# Placa_sensores.net
KiCad netlist of a schematic drawn in EAGLE
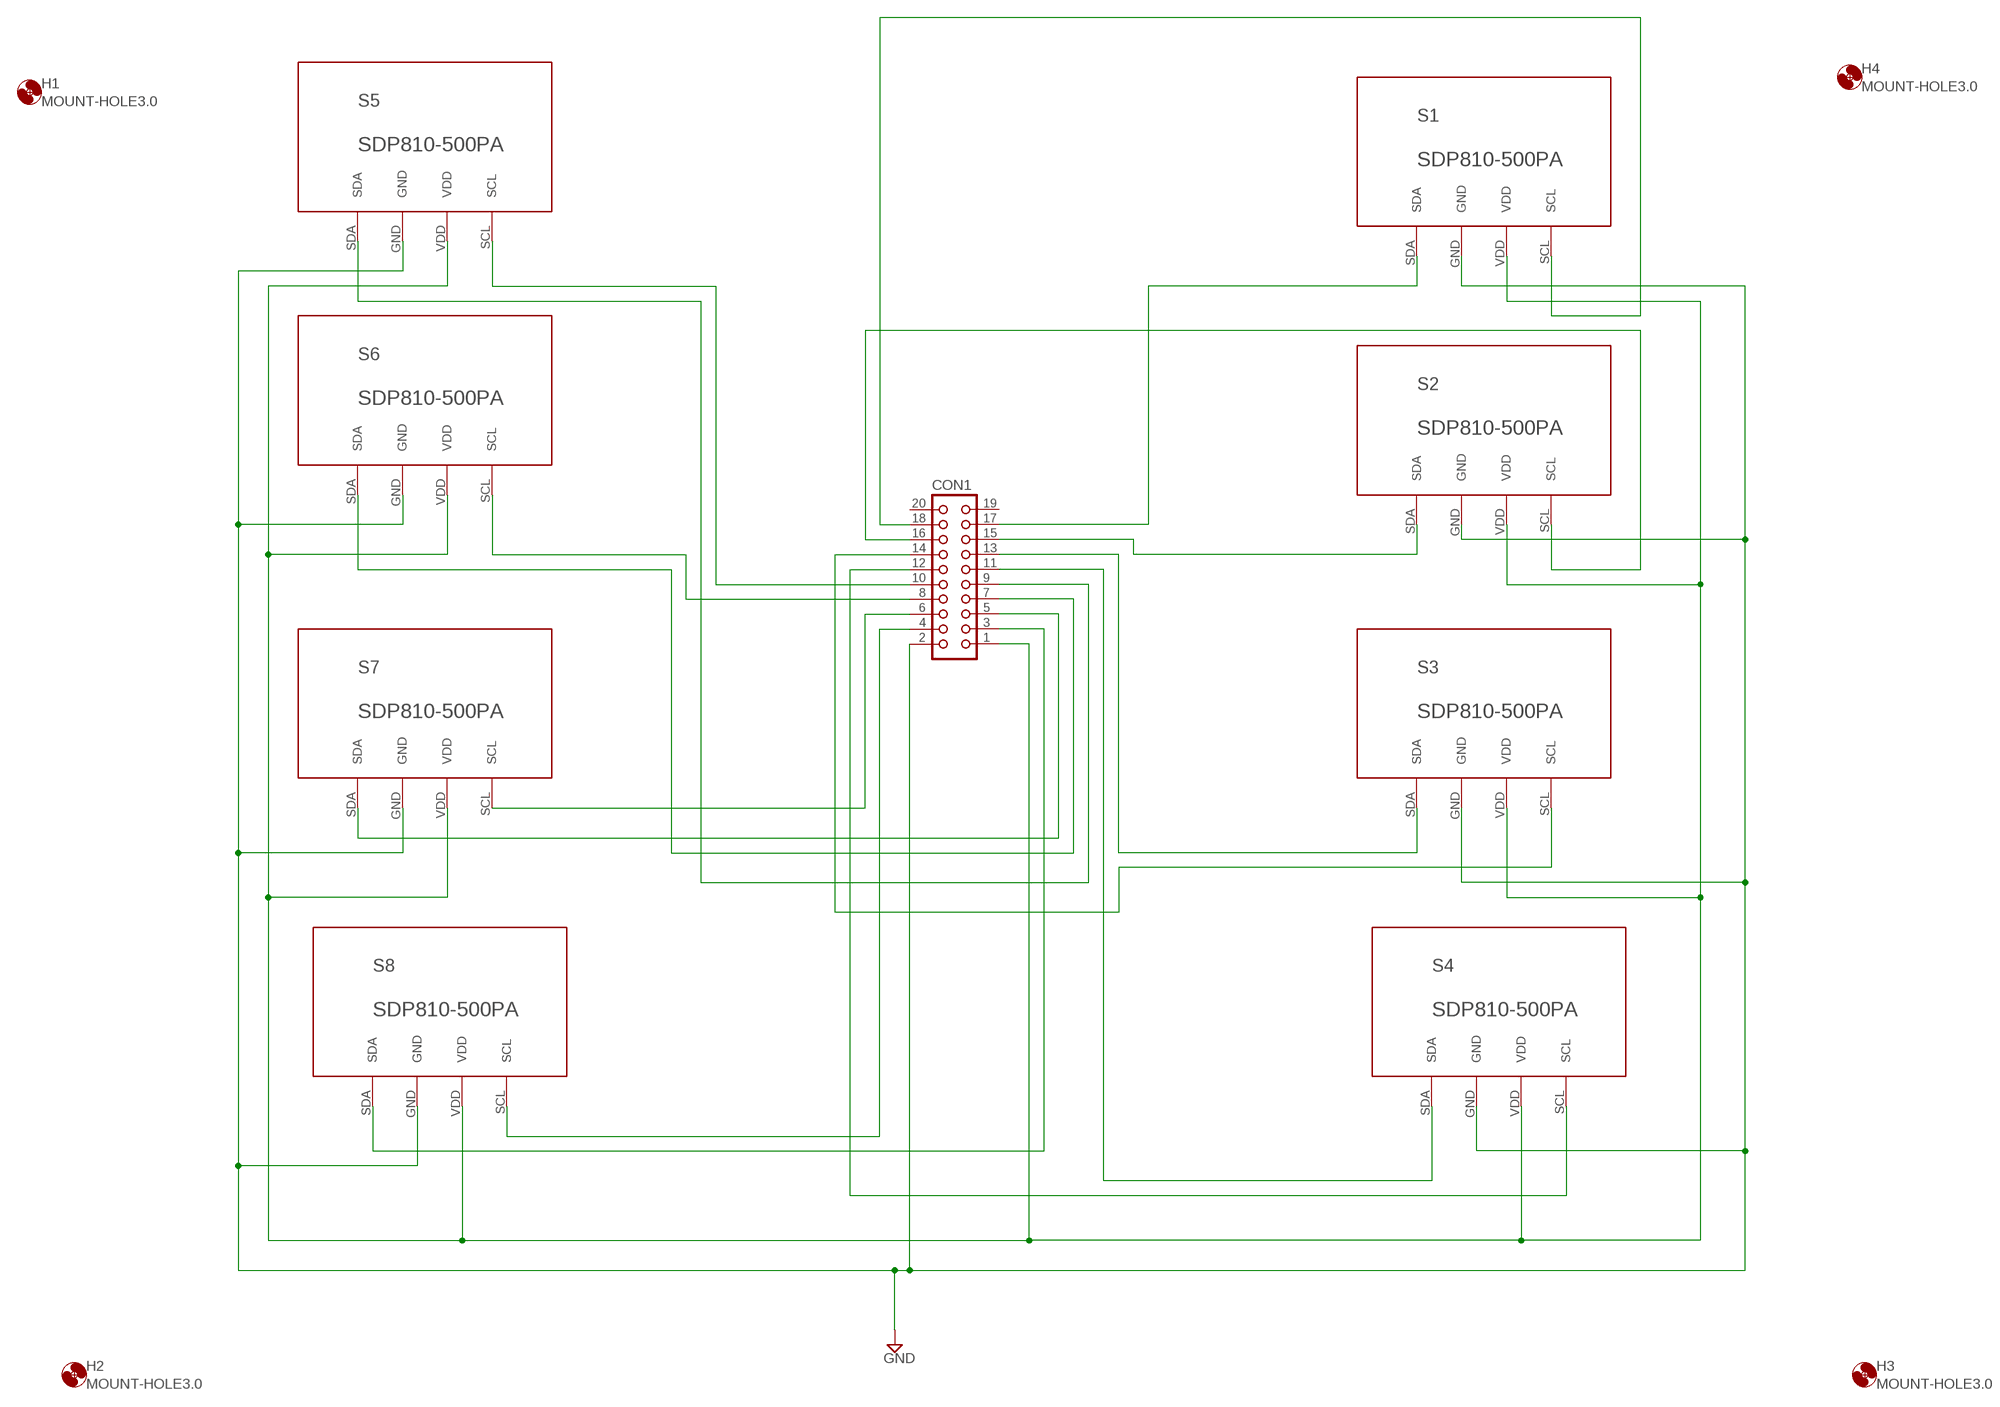
[diagram p0: schematic, sheet 1]

(export (version "E")
  (design (tool "Eeschema 10.0.6"))
  (components
    (comp (ref "CON1")
      (value "CON20")
      (footprint "eagle-import:CON20")
      (libsource (lib "eagle-import") (part "CON20"))
    )
    (comp (ref "H1")
      (value "MOUNT-HOLE3.0")
      (footprint "eagle-import:3,0")
      (libsource (lib "eagle-import") (part "MOUNT-HOLE3.0"))
    )
    (comp (ref "H2")
      (value "MOUNT-HOLE3.0")
      (footprint "eagle-import:3,0")
      (libsource (lib "eagle-import") (part "MOUNT-HOLE3.0"))
    )
    (comp (ref "H3")
      (value "MOUNT-HOLE3.0")
      (footprint "eagle-import:3,0")
      (libsource (lib "eagle-import") (part "MOUNT-HOLE3.0"))
    )
    (comp (ref "H4")
      (value "MOUNT-HOLE3.0")
      (footprint "eagle-import:3,0")
      (libsource (lib "eagle-import") (part "MOUNT-HOLE3.0"))
    )
    (comp (ref "S1")
      (value "SDP810-500PA")
      (footprint "eagle-import:SDP810-500PA")
      (libsource (lib "eagle-import") (part "SDP810-500PA"))
    )
    (comp (ref "S2")
      (value "SDP810-500PA")
      (footprint "eagle-import:SDP810-500PA")
      (libsource (lib "eagle-import") (part "SDP810-500PA"))
    )
    (comp (ref "S3")
      (value "SDP810-500PA")
      (footprint "eagle-import:SDP810-500PA")
      (libsource (lib "eagle-import") (part "SDP810-500PA"))
    )
    (comp (ref "S4")
      (value "SDP810-500PA")
      (footprint "eagle-import:SDP810-500PA")
      (libsource (lib "eagle-import") (part "SDP810-500PA"))
    )
    (comp (ref "S5")
      (value "SDP810-500PA")
      (footprint "eagle-import:SDP810-500PA")
      (libsource (lib "eagle-import") (part "SDP810-500PA"))
    )
    (comp (ref "S6")
      (value "SDP810-500PA")
      (footprint "eagle-import:SDP810-500PA")
      (libsource (lib "eagle-import") (part "SDP810-500PA"))
    )
    (comp (ref "S7")
      (value "SDP810-500PA")
      (footprint "eagle-import:SDP810-500PA")
      (libsource (lib "eagle-import") (part "SDP810-500PA"))
    )
    (comp (ref "S8")
      (value "SDP810-500PA")
      (footprint "eagle-import:SDP810-500PA")
      (libsource (lib "eagle-import") (part "SDP810-500PA"))
    )
  )
  (nets
    (net (code "1") (name "GND") (class "Default")
      (node (ref "CON1") (pin "2") (pinfunction "2_2") (pintype "passive"))
      (node (ref "S1") (pin "GND") (pinfunction "GND_GND") (pintype "bidirectional"))
      (node (ref "S2") (pin "GND") (pinfunction "GND_GND") (pintype "bidirectional"))
      (node (ref "S3") (pin "GND") (pinfunction "GND_GND") (pintype "bidirectional"))
      (node (ref "S4") (pin "GND") (pinfunction "GND_GND") (pintype "bidirectional"))
      (node (ref "S5") (pin "GND") (pinfunction "GND_GND") (pintype "bidirectional"))
      (node (ref "S6") (pin "GND") (pinfunction "GND_GND") (pintype "bidirectional"))
      (node (ref "S7") (pin "GND") (pinfunction "GND_GND") (pintype "bidirectional"))
      (node (ref "S8") (pin "GND") (pinfunction "GND_GND") (pintype "bidirectional"))
    )
    (net (code "2") (name "Net-(CON1-Pad1)") (class "Default")
      (node (ref "CON1") (pin "1") (pinfunction "1_1") (pintype "passive"))
      (node (ref "S1") (pin "VDD") (pinfunction "VDD_VDD") (pintype "bidirectional"))
      (node (ref "S2") (pin "VDD") (pinfunction "VDD_VDD") (pintype "bidirectional"))
      (node (ref "S3") (pin "VDD") (pinfunction "VDD_VDD") (pintype "bidirectional"))
      (node (ref "S4") (pin "VDD") (pinfunction "VDD_VDD") (pintype "bidirectional"))
      (node (ref "S5") (pin "VDD") (pinfunction "VDD_VDD") (pintype "bidirectional"))
      (node (ref "S6") (pin "VDD") (pinfunction "VDD_VDD") (pintype "bidirectional"))
      (node (ref "S7") (pin "VDD") (pinfunction "VDD_VDD") (pintype "bidirectional"))
      (node (ref "S8") (pin "VDD") (pinfunction "VDD_VDD") (pintype "bidirectional"))
    )
    (net (code "3") (name "Net-(CON1-Pad3)") (class "Default")
      (node (ref "CON1") (pin "3") (pinfunction "3_3") (pintype "passive"))
      (node (ref "S8") (pin "SDA") (pinfunction "SDA_SDA") (pintype "bidirectional"))
    )
    (net (code "4") (name "Net-(CON1-Pad4)") (class "Default")
      (node (ref "CON1") (pin "4") (pinfunction "4_4") (pintype "passive"))
      (node (ref "S8") (pin "SCL") (pinfunction "SCL_SCL") (pintype "bidirectional"))
    )
    (net (code "5") (name "Net-(CON1-Pad5)") (class "Default")
      (node (ref "CON1") (pin "5") (pinfunction "5_5") (pintype "passive"))
      (node (ref "S7") (pin "SDA") (pinfunction "SDA_SDA") (pintype "bidirectional"))
    )
    (net (code "6") (name "Net-(CON1-Pad6)") (class "Default")
      (node (ref "CON1") (pin "6") (pinfunction "6_6") (pintype "passive"))
      (node (ref "S7") (pin "SCL") (pinfunction "SCL_SCL") (pintype "bidirectional"))
    )
    (net (code "7") (name "Net-(CON1-Pad7)") (class "Default")
      (node (ref "CON1") (pin "7") (pinfunction "7_7") (pintype "passive"))
      (node (ref "S6") (pin "SDA") (pinfunction "SDA_SDA") (pintype "bidirectional"))
    )
    (net (code "8") (name "Net-(CON1-Pad8)") (class "Default")
      (node (ref "CON1") (pin "8") (pinfunction "8_8") (pintype "passive"))
      (node (ref "S6") (pin "SCL") (pinfunction "SCL_SCL") (pintype "bidirectional"))
    )
    (net (code "9") (name "Net-(CON1-Pad9)") (class "Default")
      (node (ref "CON1") (pin "9") (pinfunction "9_9") (pintype "passive"))
      (node (ref "S5") (pin "SDA") (pinfunction "SDA_SDA") (pintype "bidirectional"))
    )
    (net (code "10") (name "Net-(CON1-Pad10)") (class "Default")
      (node (ref "CON1") (pin "10") (pinfunction "10_10") (pintype "passive"))
      (node (ref "S5") (pin "SCL") (pinfunction "SCL_SCL") (pintype "bidirectional"))
    )
    (net (code "11") (name "Net-(CON1-Pad11)") (class "Default")
      (node (ref "CON1") (pin "11") (pinfunction "11_11") (pintype "passive"))
      (node (ref "S4") (pin "SDA") (pinfunction "SDA_SDA") (pintype "bidirectional"))
    )
    (net (code "12") (name "Net-(CON1-Pad12)") (class "Default")
      (node (ref "CON1") (pin "12") (pinfunction "12_12") (pintype "passive"))
      (node (ref "S4") (pin "SCL") (pinfunction "SCL_SCL") (pintype "bidirectional"))
    )
    (net (code "13") (name "Net-(CON1-Pad13)") (class "Default")
      (node (ref "CON1") (pin "13") (pinfunction "13_13") (pintype "passive"))
      (node (ref "S3") (pin "SDA") (pinfunction "SDA_SDA") (pintype "bidirectional"))
    )
    (net (code "14") (name "Net-(CON1-Pad14)") (class "Default")
      (node (ref "CON1") (pin "14") (pinfunction "14_14") (pintype "passive"))
      (node (ref "S3") (pin "SCL") (pinfunction "SCL_SCL") (pintype "bidirectional"))
    )
    (net (code "15") (name "Net-(CON1-Pad15)") (class "Default")
      (node (ref "CON1") (pin "15") (pinfunction "15_15") (pintype "passive"))
      (node (ref "S2") (pin "SDA") (pinfunction "SDA_SDA") (pintype "bidirectional"))
    )
    (net (code "16") (name "Net-(CON1-Pad16)") (class "Default")
      (node (ref "CON1") (pin "16") (pinfunction "16_16") (pintype "passive"))
      (node (ref "S2") (pin "SCL") (pinfunction "SCL_SCL") (pintype "bidirectional"))
    )
    (net (code "17") (name "Net-(CON1-Pad17)") (class "Default")
      (node (ref "CON1") (pin "17") (pinfunction "17_17") (pintype "passive"))
      (node (ref "S1") (pin "SDA") (pinfunction "SDA_SDA") (pintype "bidirectional"))
    )
    (net (code "18") (name "Net-(CON1-Pad18)") (class "Default")
      (node (ref "CON1") (pin "18") (pinfunction "18_18") (pintype "passive"))
      (node (ref "S1") (pin "SCL") (pinfunction "SCL_SCL") (pintype "bidirectional"))
    )
    (net (code "19") (name "unconnected-(CON1-Pad19)") (class "Default")
      (node (ref "CON1") (pin "19") (pinfunction "19_19") (pintype "passive"))
    )
    (net (code "20") (name "unconnected-(CON1-Pad20)") (class "Default")
      (node (ref "CON1") (pin "20") (pinfunction "20_20") (pintype "passive"))
    )
  )
)
